# Sht3-V12P0_reg.net
KiCad netlist of a schematic drawn in Altium Designer
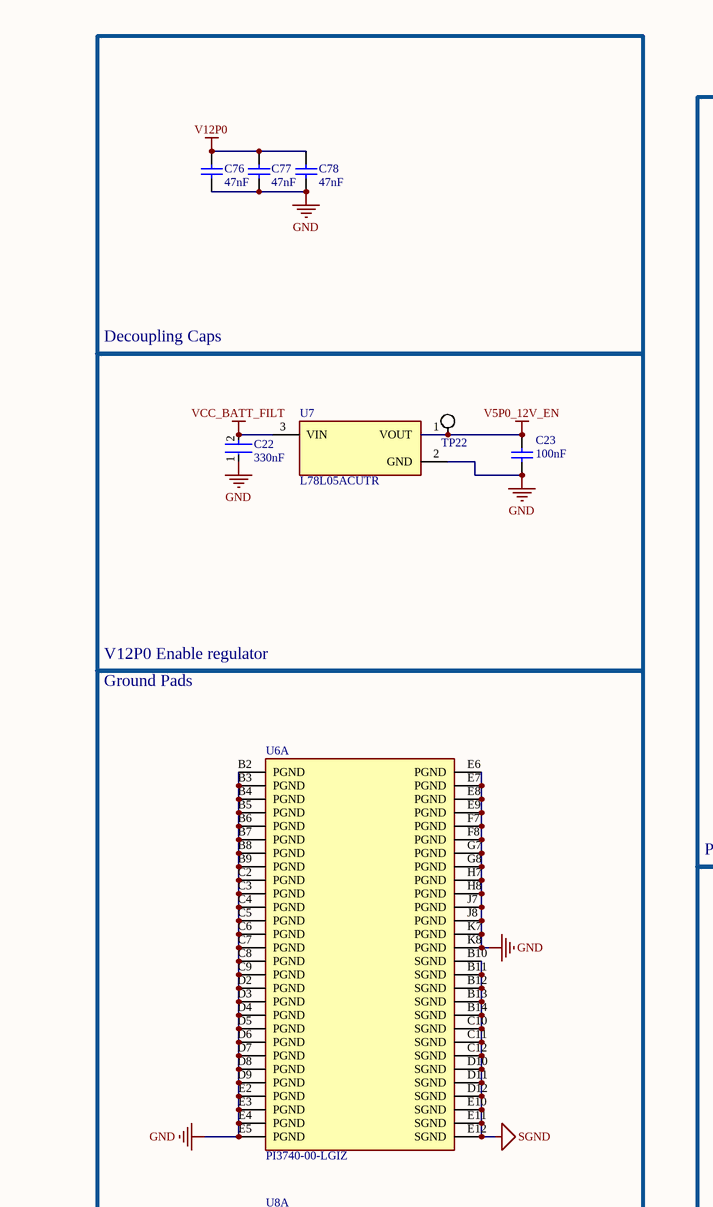
[diagram p0: Sht3-V12P0_reg.SchDoc, top left]
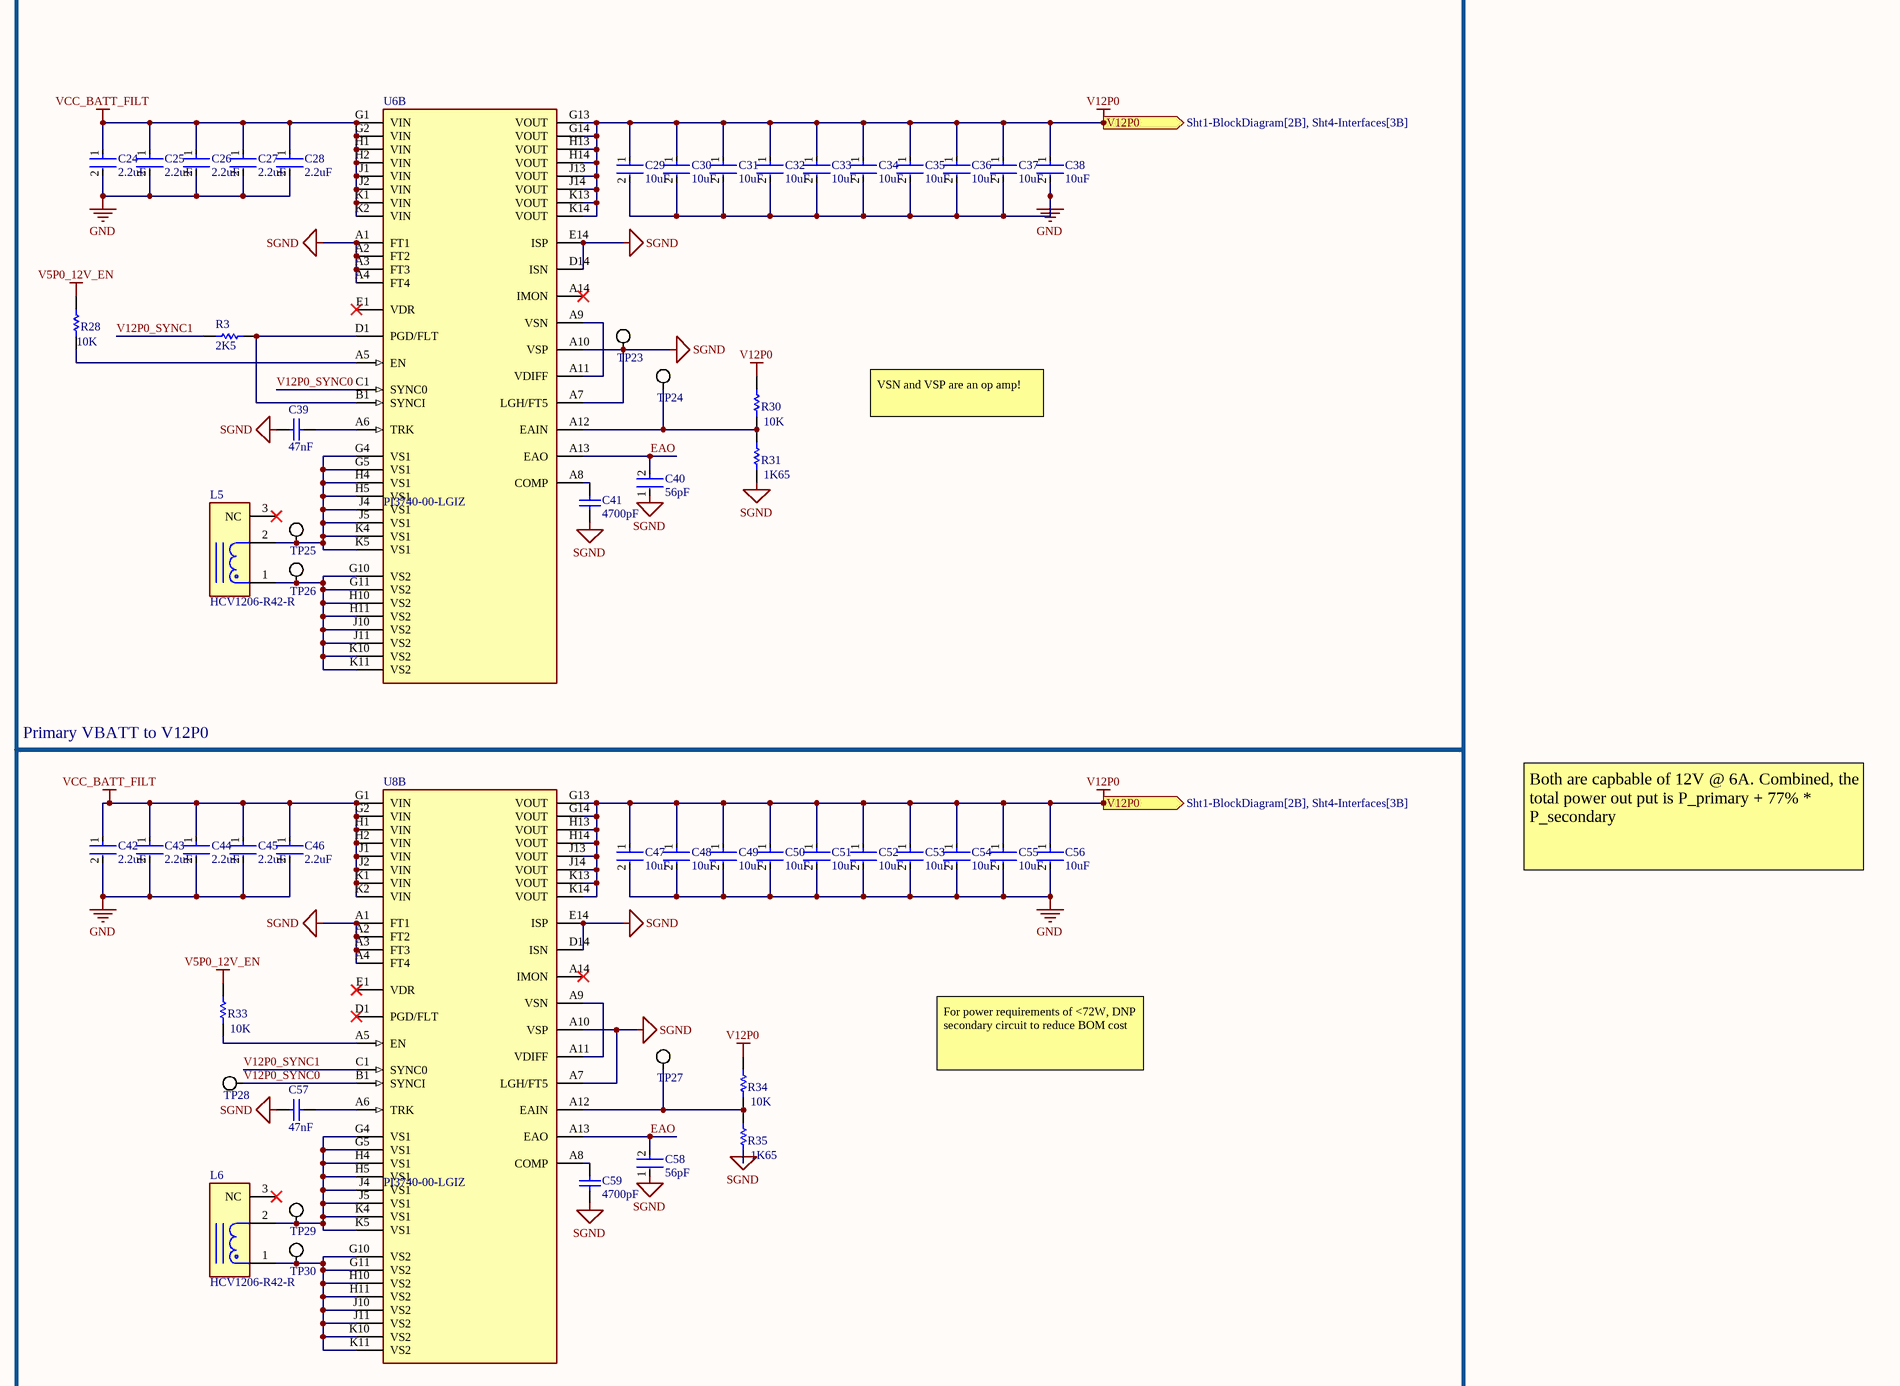
[diagram p1: Sht3-V12P0_reg.SchDoc, top right]
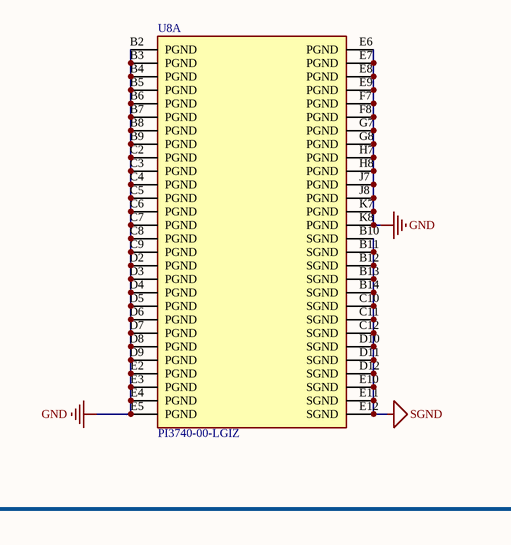
[diagram p2: Sht3-V12P0_reg.SchDoc, bottom left]
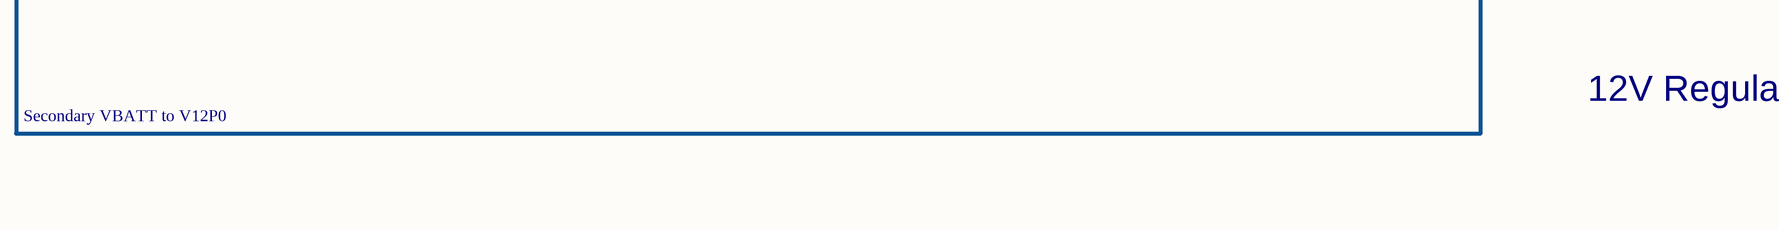
[diagram p3: Sht3-V12P0_reg.SchDoc, bottom right]

(export (version "E")
  (design (tool "Eeschema 10.0.6"))
  (components
    (comp (ref "C22")
      (value "330nF")
      (footprint "FP-C1608-080-0_1-IPC_A")
      (description "Multilayer Ceramic Capacitors 330nF ±10% 50V X7R SMD 0603")
      (fields (field (name "TOLERANCE") "10%") (field (name "VOLTAGE") "50V"))
      (libsource (lib "Altium Content Vault") (part "236180d848d6139a670b325ea6854c9"))
    )
    (comp (ref "C23")
      (value "100nF")
      (footprint "CAPC0603(1608)100_L")
      (description "CAP 100nF 100V ±10% 0603 (1608 Metric) Thickness 1mm SMD")
      (fields (field (name "TOLERANCE") "Â±10%"))
      (libsource (lib "Altium Content Vault") (part "CAP"))
    )
    (comp (ref "C24")
      (value "2.2uF")
      (footprint "FP-1210-L_3_3_0_4-W_2_5_0-IPC_B")
      (description "General Purpose Ceramic Capacitor, 1210, 2.2uF, 10%, X7R, 15%, 100V")
      (fields (field (name "TOLERANCE") "10%") (field (name "VOLTAGE") "100V"))
      (libsource (lib "Altium Content Vault") (part "b4654b650e69147ec39a6b967a45e02"))
    )
    (comp (ref "C25")
      (value "2.2uF")
      (footprint "FP-1210-L_3_3_0_4-W_2_5_0-IPC_B")
      (description "General Purpose Ceramic Capacitor, 1210, 2.2uF, 10%, X7R, 15%, 100V")
      (fields (field (name "TOLERANCE") "10%") (field (name "VOLTAGE") "100V"))
      (libsource (lib "Altium Content Vault") (part "b4654b650e69147ec39a6b967a45e02"))
    )
    (comp (ref "C26")
      (value "2.2uF")
      (footprint "FP-1210-L_3_3_0_4-W_2_5_0-IPC_B")
      (description "General Purpose Ceramic Capacitor, 1210, 2.2uF, 10%, X7R, 15%, 100V")
      (fields (field (name "TOLERANCE") "10%") (field (name "VOLTAGE") "100V"))
      (libsource (lib "Altium Content Vault") (part "b4654b650e69147ec39a6b967a45e02"))
    )
    (comp (ref "C27")
      (value "2.2uF")
      (footprint "FP-1210-L_3_3_0_4-W_2_5_0-IPC_B")
      (description "General Purpose Ceramic Capacitor, 1210, 2.2uF, 10%, X7R, 15%, 100V")
      (fields (field (name "TOLERANCE") "10%") (field (name "VOLTAGE") "100V"))
      (libsource (lib "Altium Content Vault") (part "b4654b650e69147ec39a6b967a45e02"))
    )
    (comp (ref "C28")
      (value "2.2uF")
      (footprint "FP-1210-L_3_3_0_4-W_2_5_0-IPC_B")
      (description "General Purpose Ceramic Capacitor, 1210, 2.2uF, 10%, X7R, 15%, 100V")
      (fields (field (name "TOLERANCE") "10%") (field (name "VOLTAGE") "100V"))
      (libsource (lib "Altium Content Vault") (part "b4654b650e69147ec39a6b967a45e02"))
    )
    (comp (ref "C29")
      (value "10uF")
      (footprint "FP-GRM32-MFG")
      (description "CAP CER 10UF 50V X7R 1210")
      (fields (field (name "TOLERANCE") "10%") (field (name "MANUFACTURER PART NUMBER") "GRM32ER71H106KA12L"))
      (libsource (lib "Altium Content Vault") (part "11868f565c42a9108669ba33697ecf6"))
    )
    (comp (ref "C30")
      (value "10uF")
      (footprint "FP-GRM32-MFG")
      (description "CAP CER 10UF 50V X7R 1210")
      (fields (field (name "TOLERANCE") "10%") (field (name "MANUFACTURER PART NUMBER") "GRM32ER71H106KA12L"))
      (libsource (lib "Altium Content Vault") (part "11868f565c42a9108669ba33697ecf6"))
    )
    (comp (ref "C31")
      (value "10uF")
      (footprint "FP-GRM32-MFG")
      (description "CAP CER 10UF 50V X7R 1210")
      (fields (field (name "TOLERANCE") "10%") (field (name "MANUFACTURER PART NUMBER") "GRM32ER71H106KA12L"))
      (libsource (lib "Altium Content Vault") (part "11868f565c42a9108669ba33697ecf6"))
    )
    (comp (ref "C32")
      (value "10uF")
      (footprint "FP-GRM32-MFG")
      (description "CAP CER 10UF 50V X7R 1210")
      (fields (field (name "TOLERANCE") "10%") (field (name "MANUFACTURER PART NUMBER") "GRM32ER71H106KA12L"))
      (libsource (lib "Altium Content Vault") (part "11868f565c42a9108669ba33697ecf6"))
    )
    (comp (ref "C33")
      (value "10uF")
      (footprint "FP-GRM32-MFG")
      (description "CAP CER 10UF 50V X7R 1210")
      (fields (field (name "TOLERANCE") "10%") (field (name "MANUFACTURER PART NUMBER") "GRM32ER71H106KA12L"))
      (libsource (lib "Altium Content Vault") (part "11868f565c42a9108669ba33697ecf6"))
    )
    (comp (ref "C34")
      (value "10uF")
      (footprint "FP-GRM32-MFG")
      (description "CAP CER 10UF 50V X7R 1210")
      (fields (field (name "TOLERANCE") "10%") (field (name "MANUFACTURER PART NUMBER") "GRM32ER71H106KA12L"))
      (libsource (lib "Altium Content Vault") (part "11868f565c42a9108669ba33697ecf6"))
    )
    (comp (ref "C35")
      (value "10uF")
      (footprint "FP-GRM32-MFG")
      (description "CAP CER 10UF 50V X7R 1210")
      (fields (field (name "TOLERANCE") "10%") (field (name "MANUFACTURER PART NUMBER") "GRM32ER71H106KA12L"))
      (libsource (lib "Altium Content Vault") (part "11868f565c42a9108669ba33697ecf6"))
    )
    (comp (ref "C36")
      (value "10uF")
      (footprint "FP-GRM32-MFG")
      (description "CAP CER 10UF 50V X7R 1210")
      (fields (field (name "TOLERANCE") "10%") (field (name "MANUFACTURER PART NUMBER") "GRM32ER71H106KA12L"))
      (libsource (lib "Altium Content Vault") (part "11868f565c42a9108669ba33697ecf6"))
    )
    (comp (ref "C37")
      (value "10uF")
      (footprint "FP-GRM32-MFG")
      (description "CAP CER 10UF 50V X7R 1210")
      (fields (field (name "TOLERANCE") "10%") (field (name "MANUFACTURER PART NUMBER") "GRM32ER71H106KA12L"))
      (libsource (lib "Altium Content Vault") (part "11868f565c42a9108669ba33697ecf6"))
    )
    (comp (ref "C38")
      (value "10uF")
      (footprint "FP-GRM32-MFG")
      (description "CAP CER 10UF 50V X7R 1210")
      (fields (field (name "TOLERANCE") "10%") (field (name "MANUFACTURER PART NUMBER") "GRM32ER71H106KA12L"))
      (libsource (lib "Altium Content Vault") (part "11868f565c42a9108669ba33697ecf6"))
    )
    (comp (ref "C39")
      (value "47nF")
      (footprint "CAPC1608X90X35LL10T15")
      (description "47nF 0603")
      (fields (field (name "MANUFACTURER") "Murata") (field (name "PART NUMBER") "GRM188R71E473KA01D"))
      (libsource (lib "Altium Content Vault") (part "CAP"))
    )
    (comp (ref "C40")
      (value "56pF")
      (footprint "FP-C1608-080-0_1-IPC_C")
      (description "Multilayer Ceramic Capacitors 56pF ±5% 50V C0G SMD 0603")
      (fields (field (name "TOLERANCE") "5%"))
      (libsource (lib "Altium Content Vault") (part "236180d848d6139a670b325ea6854c9"))
    )
    (comp (ref "C41")
      (value "4700pF")
      (footprint "CAPC1608X90X35ML10T15")
      (description "4700pF 0603")
      (fields (field (name "PART NUMBER") "GRM188R72A472KA01D") (field (name "MANUFACTURER") "Murata"))
      (libsource (lib "Altium Content Vault") (part "CAP"))
    )
    (comp (ref "C42")
      (value "2.2uF")
      (footprint "FP-1210-L_3_3_0_4-W_2_5_0-IPC_B")
      (description "General Purpose Ceramic Capacitor, 1210, 2.2uF, 10%, X7R, 15%, 100V")
      (fields (field (name "TOLERANCE") "10%") (field (name "VOLTAGE") "100V"))
      (libsource (lib "Altium Content Vault") (part "b4654b650e69147ec39a6b967a45e02"))
    )
    (comp (ref "C43")
      (value "2.2uF")
      (footprint "FP-1210-L_3_3_0_4-W_2_5_0-IPC_B")
      (description "General Purpose Ceramic Capacitor, 1210, 2.2uF, 10%, X7R, 15%, 100V")
      (fields (field (name "TOLERANCE") "10%") (field (name "VOLTAGE") "100V"))
      (libsource (lib "Altium Content Vault") (part "b4654b650e69147ec39a6b967a45e02"))
    )
    (comp (ref "C44")
      (value "2.2uF")
      (footprint "FP-1210-L_3_3_0_4-W_2_5_0-IPC_B")
      (description "General Purpose Ceramic Capacitor, 1210, 2.2uF, 10%, X7R, 15%, 100V")
      (fields (field (name "TOLERANCE") "10%") (field (name "VOLTAGE") "100V"))
      (libsource (lib "Altium Content Vault") (part "b4654b650e69147ec39a6b967a45e02"))
    )
    (comp (ref "C45")
      (value "2.2uF")
      (footprint "FP-1210-L_3_3_0_4-W_2_5_0-IPC_B")
      (description "General Purpose Ceramic Capacitor, 1210, 2.2uF, 10%, X7R, 15%, 100V")
      (fields (field (name "TOLERANCE") "10%") (field (name "VOLTAGE") "100V"))
      (libsource (lib "Altium Content Vault") (part "b4654b650e69147ec39a6b967a45e02"))
    )
    (comp (ref "C46")
      (value "2.2uF")
      (footprint "FP-1210-L_3_3_0_4-W_2_5_0-IPC_B")
      (description "General Purpose Ceramic Capacitor, 1210, 2.2uF, 10%, X7R, 15%, 100V")
      (fields (field (name "TOLERANCE") "10%") (field (name "VOLTAGE") "100V"))
      (libsource (lib "Altium Content Vault") (part "b4654b650e69147ec39a6b967a45e02"))
    )
    (comp (ref "C47")
      (value "10uF")
      (footprint "FP-GRM32-MFG")
      (description "CAP CER 10UF 50V X7R 1210")
      (fields (field (name "TOLERANCE") "10%") (field (name "MANUFACTURER PART NUMBER") "GRM32ER71H106KA12L"))
      (libsource (lib "Altium Content Vault") (part "11868f565c42a9108669ba33697ecf6"))
    )
    (comp (ref "C48")
      (value "10uF")
      (footprint "FP-GRM32-MFG")
      (description "CAP CER 10UF 50V X7R 1210")
      (fields (field (name "TOLERANCE") "10%") (field (name "MANUFACTURER PART NUMBER") "GRM32ER71H106KA12L"))
      (libsource (lib "Altium Content Vault") (part "11868f565c42a9108669ba33697ecf6"))
    )
    (comp (ref "C49")
      (value "10uF")
      (footprint "FP-GRM32-MFG")
      (description "CAP CER 10UF 50V X7R 1210")
      (fields (field (name "TOLERANCE") "10%") (field (name "MANUFACTURER PART NUMBER") "GRM32ER71H106KA12L"))
      (libsource (lib "Altium Content Vault") (part "11868f565c42a9108669ba33697ecf6"))
    )
    (comp (ref "C50")
      (value "10uF")
      (footprint "FP-GRM32-MFG")
      (description "CAP CER 10UF 50V X7R 1210")
      (fields (field (name "TOLERANCE") "10%") (field (name "MANUFACTURER PART NUMBER") "GRM32ER71H106KA12L"))
      (libsource (lib "Altium Content Vault") (part "11868f565c42a9108669ba33697ecf6"))
    )
    (comp (ref "C51")
      (value "10uF")
      (footprint "FP-GRM32-MFG")
      (description "CAP CER 10UF 50V X7R 1210")
      (fields (field (name "TOLERANCE") "10%") (field (name "MANUFACTURER PART NUMBER") "GRM32ER71H106KA12L"))
      (libsource (lib "Altium Content Vault") (part "11868f565c42a9108669ba33697ecf6"))
    )
    (comp (ref "C52")
      (value "10uF")
      (footprint "FP-GRM32-MFG")
      (description "CAP CER 10UF 50V X7R 1210")
      (fields (field (name "TOLERANCE") "10%") (field (name "MANUFACTURER PART NUMBER") "GRM32ER71H106KA12L"))
      (libsource (lib "Altium Content Vault") (part "11868f565c42a9108669ba33697ecf6"))
    )
    (comp (ref "C53")
      (value "10uF")
      (footprint "FP-GRM32-MFG")
      (description "CAP CER 10UF 50V X7R 1210")
      (fields (field (name "TOLERANCE") "10%") (field (name "MANUFACTURER PART NUMBER") "GRM32ER71H106KA12L"))
      (libsource (lib "Altium Content Vault") (part "11868f565c42a9108669ba33697ecf6"))
    )
    (comp (ref "C54")
      (value "10uF")
      (footprint "FP-GRM32-MFG")
      (description "CAP CER 10UF 50V X7R 1210")
      (fields (field (name "TOLERANCE") "10%") (field (name "MANUFACTURER PART NUMBER") "GRM32ER71H106KA12L"))
      (libsource (lib "Altium Content Vault") (part "11868f565c42a9108669ba33697ecf6"))
    )
    (comp (ref "C55")
      (value "10uF")
      (footprint "FP-GRM32-MFG")
      (description "CAP CER 10UF 50V X7R 1210")
      (fields (field (name "TOLERANCE") "10%") (field (name "MANUFACTURER PART NUMBER") "GRM32ER71H106KA12L"))
      (libsource (lib "Altium Content Vault") (part "11868f565c42a9108669ba33697ecf6"))
    )
    (comp (ref "C56")
      (value "10uF")
      (footprint "FP-GRM32-MFG")
      (description "CAP CER 10UF 50V X7R 1210")
      (fields (field (name "TOLERANCE") "10%") (field (name "MANUFACTURER PART NUMBER") "GRM32ER71H106KA12L"))
      (libsource (lib "Altium Content Vault") (part "11868f565c42a9108669ba33697ecf6"))
    )
    (comp (ref "C57")
      (value "47nF")
      (footprint "CAPC1608X90X35LL10T15")
      (description "47nF 0603")
      (fields (field (name "MANUFACTURER") "Murata") (field (name "PART NUMBER") "GRM188R71E473KA01D"))
      (libsource (lib "Altium Content Vault") (part "CAP"))
    )
    (comp (ref "C58")
      (value "56pF")
      (footprint "FP-C1608-080-0_1-IPC_C")
      (description "Multilayer Ceramic Capacitors 56pF ±5% 50V C0G SMD 0603")
      (fields (field (name "TOLERANCE") "5%"))
      (libsource (lib "Altium Content Vault") (part "236180d848d6139a670b325ea6854c9"))
    )
    (comp (ref "C59")
      (value "4700pF")
      (footprint "CAPC1608X90X35ML10T15")
      (description "4700pF 0603")
      (fields (field (name "PART NUMBER") "GRM188R72A472KA01D") (field (name "MANUFACTURER") "Murata"))
      (libsource (lib "Altium Content Vault") (part "CAP"))
    )
    (comp (ref "C76")
      (value "47nF")
      (footprint "CAPC1608X90X35LL10T15")
      (description "47nF 0603")
      (fields (field (name "MANUFACTURER") "Murata") (field (name "PART NUMBER") "GRM188R71E473KA01D"))
      (libsource (lib "Altium Content Vault") (part "CAP"))
    )
    (comp (ref "C77")
      (value "47nF")
      (footprint "CAPC1608X90X35LL10T15")
      (description "47nF 0603")
      (fields (field (name "MANUFACTURER") "Murata") (field (name "PART NUMBER") "GRM188R71E473KA01D"))
      (libsource (lib "Altium Content Vault") (part "CAP"))
    )
    (comp (ref "C78")
      (value "47nF")
      (footprint "CAPC1608X90X35LL10T15")
      (description "47nF 0603")
      (fields (field (name "MANUFACTURER") "Murata") (field (name "PART NUMBER") "GRM188R71E473KA01D"))
      (libsource (lib "Altium Content Vault") (part "CAP"))
    )
    (comp (ref "L5")
      (value "HCV1206-R42-R")
      (footprint "FP-HCV1206-R42-R-MFG")
      (description "HCV1206-R42-R -FIXED IND 420NH 16A 3.15 MOHM")
      (fields (field (name "TOLERANCE") "10%"))
      (libsource (lib "Altium Content Vault") (part "37f71924ba6560a669f32c2ee7c419d"))
    )
    (comp (ref "L6")
      (value "HCV1206-R42-R")
      (footprint "FP-HCV1206-R42-R-MFG")
      (description "FIXED IND 420NH 16A 3.15 MOHM")
      (fields (field (name "TOLERANCE") "10%"))
      (libsource (lib "Altium Content Vault") (part "37f71924ba6560a669f32c2ee7c419d"))
    )
    (comp (ref "R3")
      (value "2K5")
      (footprint "RESC1608X55X25NL10T15")
      (description "2.5K 0603")
      (fields (field (name "MANUFACTURER") "Yageo") (field (name "PART NUMBER") "RC0603FR-072K55L"))
      (libsource (lib "Altium Content Vault") (part "RES"))
    )
    (comp (ref "R28")
      (value "10K")
      (footprint "RESC1609X50X30NL8T20")
      (description "Chip Resistor, 10 KOhm, +/- 1%, 100 mW, -55 to 155 degC, 0603 (1608 Metric), RoHS, Tape and Reel")
      (fields (field (name "MANUFACTURER") "Vishay Semiconductor"))
      (libsource (lib "Altium Content Vault") (part "RES-2"))
    )
    (comp (ref "R30")
      (value "10K")
      (footprint "RESC1609X50X30NL8T20")
      (description "Chip Resistor, 10 KOhm, +/- 1%, 100 mW, -55 to 155 degC, 0603 (1608 Metric), RoHS, Tape and Reel")
      (fields (field (name "MANUFACTURER") "Vishay Semiconductor"))
      (libsource (lib "Altium Content Vault") (part "RES-2"))
    )
    (comp (ref "R31")
      (value "1K65")
      (footprint "RESC1608X55X25ML10T15")
      (description "1.65k 0603")
      (fields (field (name "PART NUMBER") "RC0603FR-071K65L") (field (name "MANUFACTURER") "Yageo"))
      (libsource (lib "Altium Content Vault") (part "RES"))
    )
    (comp (ref "R33")
      (value "10K")
      (footprint "RESC1609X50X30NL8T20")
      (description "Chip Resistor, 10 KOhm, +/- 1%, 100 mW, -55 to 155 degC, 0603 (1608 Metric), RoHS, Tape and Reel")
      (fields (field (name "MANUFACTURER") "Vishay Semiconductor"))
      (libsource (lib "Altium Content Vault") (part "RES-2"))
    )
    (comp (ref "R34")
      (value "10K")
      (footprint "RESC1609X50X30NL8T20")
      (description "Chip Resistor, 10 KOhm, +/- 1%, 100 mW, -55 to 155 degC, 0603 (1608 Metric), RoHS, Tape and Reel")
      (fields (field (name "MANUFACTURER") "Vishay Semiconductor"))
      (libsource (lib "Altium Content Vault") (part "RES-2"))
    )
    (comp (ref "R35")
      (value "1K65")
      (footprint "RESC1608X55X25ML10T15")
      (description "1.65k 0603")
      (fields (field (name "PART NUMBER") "RC0603FR-071K65L") (field (name "MANUFACTURER") "Yageo"))
      (libsource (lib "Altium Content Vault") (part "RES"))
    )
    (comp (ref "TP22")
      (value "Test Point Pad")
      (footprint "Test Point Pad")
      (description "Test point, Pad, 28 mil")
      (libsource (lib "CMR_PCB_Components") (part "Test Point Pad"))
    )
    (comp (ref "TP23")
      (value "Test Point Pad")
      (footprint "Test Point Pad")
      (description "Test point, Pad, 28 mil")
      (libsource (lib "CMR_PCB_Components") (part "Test Point Pad"))
    )
    (comp (ref "TP24")
      (value "Test Point Pad")
      (footprint "Test Point Pad")
      (description "Test point, Pad, 28 mil")
      (libsource (lib "CMR_PCB_Components") (part "Test Point Pad"))
    )
    (comp (ref "TP25")
      (value "Test Point Pad")
      (footprint "Test Point Pad")
      (description "Test point, Pad, 28 mil")
      (libsource (lib "CMR_PCB_Components") (part "Test Point Pad"))
    )
    (comp (ref "TP26")
      (value "Test Point Pad")
      (footprint "Test Point Pad")
      (description "Test point, Pad, 28 mil")
      (libsource (lib "CMR_PCB_Components") (part "Test Point Pad"))
    )
    (comp (ref "TP27")
      (value "Test Point Pad")
      (footprint "Test Point Pad")
      (description "Test point, Pad, 28 mil")
      (libsource (lib "CMR_PCB_Components") (part "Test Point Pad"))
    )
    (comp (ref "TP28")
      (value "Test Point Pad")
      (footprint "Test Point Pad")
      (description "Test point, Pad, 28 mil")
      (libsource (lib "CMR_PCB_Components") (part "Test Point Pad"))
    )
    (comp (ref "TP29")
      (value "Test Point Pad")
      (footprint "Test Point Pad")
      (description "Test point, Pad, 28 mil")
      (libsource (lib "CMR_PCB_Components") (part "Test Point Pad"))
    )
    (comp (ref "TP30")
      (value "Test Point Pad")
      (footprint "Test Point Pad")
      (description "Test point, Pad, 28 mil")
      (libsource (lib "CMR_PCB_Components") (part "Test Point Pad"))
    )
    (comp (ref "U6")
      (value "PI3740-00-LGIZ")
      (footprint "FP-PI3740-00-LGIZ-MFG")
      (description "DC DC CONVERTER 10-50V")
      (libsource (lib "Altium Content Vault") (part "1066ae71189b305fd66a514a457717d"))
    )
    (comp (ref "U7")
      (value "L78L05ACUTR")
      (footprint "FP-SOT-89-7098166-MFG")
      (description "IC REG LINEAR 5V 100MA SOT89-3")
      (libsource (lib "Altium Content Vault") (part "ae6bee9076d4e2dbe8e374331bf90c1"))
    )
    (comp (ref "U8")
      (value "PI3740-00-LGIZ")
      (footprint "FP-PI3740-00-LGIZ-MFG")
      (description "DC DC CONVERTER 10-50V")
      (libsource (lib "Altium Content Vault") (part "1066ae71189b305fd66a514a457717d"))
    )
  )
  (nets
    (net (code "1") (name "/EAO") (class "Default")
      (node (ref "C40") (pin "2") (pinfunction "2_2") (pintype "passive"))
      (node (ref "C58") (pin "2") (pinfunction "2_2") (pintype "passive"))
      (node (ref "U6") (pin "A13") (pinfunction "EAO_A13") (pintype "passive"))
      (node (ref "U8") (pin "A13") (pinfunction "EAO_A13") (pintype "passive"))
    )
    (net (code "2") (name "/V12P0_SYNC0") (class "Default")
      (node (ref "TP28") (pin "1") (pinfunction "1_1") (pintype "passive"))
      (node (ref "U6") (pin "C1") (pinfunction "SYNC0_C1") (pintype "input"))
      (node (ref "U8") (pin "B1") (pinfunction "SYNCI_B1") (pintype "input"))
    )
    (net (code "3") (name "/V12P0_SYNC1") (class "Default")
      (node (ref "R3") (pin "1") (pinfunction "1_1") (pintype "passive"))
      (node (ref "U8") (pin "C1") (pinfunction "SYNC0_C1") (pintype "input"))
    )
    (net (code "4") (name "GND") (class "Default")
      (node (ref "C22") (pin "1") (pinfunction "1_1") (pintype "passive"))
      (node (ref "C23") (pin "1") (pinfunction "1_1") (pintype "passive"))
      (node (ref "C24") (pin "2") (pinfunction "2_2") (pintype "passive"))
      (node (ref "C25") (pin "2") (pinfunction "2_2") (pintype "passive"))
      (node (ref "C26") (pin "2") (pinfunction "2_2") (pintype "passive"))
      (node (ref "C27") (pin "2") (pinfunction "2_2") (pintype "passive"))
      (node (ref "C28") (pin "2") (pinfunction "2_2") (pintype "passive"))
      (node (ref "C29") (pin "2") (pinfunction "2_2") (pintype "passive"))
      (node (ref "C30") (pin "2") (pinfunction "2_2") (pintype "passive"))
      (node (ref "C31") (pin "2") (pinfunction "2_2") (pintype "passive"))
      (node (ref "C32") (pin "2") (pinfunction "2_2") (pintype "passive"))
      (node (ref "C33") (pin "2") (pinfunction "2_2") (pintype "passive"))
      (node (ref "C34") (pin "2") (pinfunction "2_2") (pintype "passive"))
      (node (ref "C35") (pin "2") (pinfunction "2_2") (pintype "passive"))
      (node (ref "C36") (pin "2") (pinfunction "2_2") (pintype "passive"))
      (node (ref "C37") (pin "2") (pinfunction "2_2") (pintype "passive"))
      (node (ref "C38") (pin "2") (pinfunction "2_2") (pintype "passive"))
      (node (ref "C42") (pin "2") (pinfunction "2_2") (pintype "passive"))
      (node (ref "C43") (pin "2") (pinfunction "2_2") (pintype "passive"))
      (node (ref "C44") (pin "2") (pinfunction "2_2") (pintype "passive"))
      (node (ref "C45") (pin "2") (pinfunction "2_2") (pintype "passive"))
      (node (ref "C46") (pin "2") (pinfunction "2_2") (pintype "passive"))
      (node (ref "C47") (pin "2") (pinfunction "2_2") (pintype "passive"))
      (node (ref "C48") (pin "2") (pinfunction "2_2") (pintype "passive"))
      (node (ref "C49") (pin "2") (pinfunction "2_2") (pintype "passive"))
      (node (ref "C50") (pin "2") (pinfunction "2_2") (pintype "passive"))
      (node (ref "C51") (pin "2") (pinfunction "2_2") (pintype "passive"))
      (node (ref "C52") (pin "2") (pinfunction "2_2") (pintype "passive"))
      (node (ref "C53") (pin "2") (pinfunction "2_2") (pintype "passive"))
      (node (ref "C54") (pin "2") (pinfunction "2_2") (pintype "passive"))
      (node (ref "C55") (pin "2") (pinfunction "2_2") (pintype "passive"))
      (node (ref "C56") (pin "2") (pinfunction "2_2") (pintype "passive"))
      (node (ref "C76") (pin "1") (pinfunction "1_1") (pintype "passive"))
      (node (ref "C77") (pin "1") (pinfunction "1_1") (pintype "passive"))
      (node (ref "C78") (pin "1") (pinfunction "1_1") (pintype "passive"))
      (node (ref "U6") (pin "B2") (pinfunction "PGND_B2") (pintype "power_in"))
      (node (ref "U6") (pin "B3") (pinfunction "PGND_B3") (pintype "power_in"))
      (node (ref "U6") (pin "B4") (pinfunction "PGND_B4") (pintype "power_in"))
      (node (ref "U6") (pin "B5") (pinfunction "PGND_B5") (pintype "power_in"))
      (node (ref "U6") (pin "B6") (pinfunction "PGND_B6") (pintype "power_in"))
      (node (ref "U6") (pin "B7") (pinfunction "PGND_B7") (pintype "power_in"))
      (node (ref "U6") (pin "B8") (pinfunction "PGND_B8") (pintype "power_in"))
      (node (ref "U6") (pin "B9") (pinfunction "PGND_B9") (pintype "power_in"))
      (node (ref "U6") (pin "C2") (pinfunction "PGND_C2") (pintype "power_in"))
      (node (ref "U6") (pin "C3") (pinfunction "PGND_C3") (pintype "power_in"))
      (node (ref "U6") (pin "C4") (pinfunction "PGND_C4") (pintype "power_in"))
      (node (ref "U6") (pin "C5") (pinfunction "PGND_C5") (pintype "power_in"))
      (node (ref "U6") (pin "C6") (pinfunction "PGND_C6") (pintype "power_in"))
      (node (ref "U6") (pin "C7") (pinfunction "PGND_C7") (pintype "power_in"))
      (node (ref "U6") (pin "C8") (pinfunction "PGND_C8") (pintype "power_in"))
      (node (ref "U6") (pin "C9") (pinfunction "PGND_C9") (pintype "power_in"))
      (node (ref "U6") (pin "D2") (pinfunction "PGND_D2") (pintype "power_in"))
      (node (ref "U6") (pin "D3") (pinfunction "PGND_D3") (pintype "power_in"))
      (node (ref "U6") (pin "D4") (pinfunction "PGND_D4") (pintype "power_in"))
      (node (ref "U6") (pin "D5") (pinfunction "PGND_D5") (pintype "power_in"))
      (node (ref "U6") (pin "D6") (pinfunction "PGND_D6") (pintype "power_in"))
      (node (ref "U6") (pin "D7") (pinfunction "PGND_D7") (pintype "power_in"))
      (node (ref "U6") (pin "D8") (pinfunction "PGND_D8") (pintype "power_in"))
      (node (ref "U6") (pin "D9") (pinfunction "PGND_D9") (pintype "power_in"))
      (node (ref "U6") (pin "E2") (pinfunction "PGND_E2") (pintype "power_in"))
      (node (ref "U6") (pin "E3") (pinfunction "PGND_E3") (pintype "power_in"))
      (node (ref "U6") (pin "E4") (pinfunction "PGND_E4") (pintype "power_in"))
      (node (ref "U6") (pin "E5") (pinfunction "PGND_E5") (pintype "power_in"))
      (node (ref "U6") (pin "E6") (pinfunction "PGND_E6") (pintype "power_in"))
      (node (ref "U6") (pin "E7") (pinfunction "PGND_E7") (pintype "power_in"))
      (node (ref "U6") (pin "E8") (pinfunction "PGND_E8") (pintype "power_in"))
      (node (ref "U6") (pin "E9") (pinfunction "PGND_E9") (pintype "power_in"))
      (node (ref "U6") (pin "F7") (pinfunction "PGND_F7") (pintype "power_in"))
      (node (ref "U6") (pin "F8") (pinfunction "PGND_F8") (pintype "power_in"))
      (node (ref "U6") (pin "G7") (pinfunction "PGND_G7") (pintype "power_in"))
      (node (ref "U6") (pin "G8") (pinfunction "PGND_G8") (pintype "power_in"))
      (node (ref "U6") (pin "H7") (pinfunction "PGND_H7") (pintype "power_in"))
      (node (ref "U6") (pin "H8") (pinfunction "PGND_H8") (pintype "power_in"))
      (node (ref "U6") (pin "J7") (pinfunction "PGND_J7") (pintype "power_in"))
      (node (ref "U6") (pin "J8") (pinfunction "PGND_J8") (pintype "power_in"))
      (node (ref "U6") (pin "K7") (pinfunction "PGND_K7") (pintype "power_in"))
      (node (ref "U6") (pin "K8") (pinfunction "PGND_K8") (pintype "power_in"))
      (node (ref "U7") (pin "2") (pinfunction "GND_2") (pintype "power_in"))
      (node (ref "U8") (pin "B2") (pinfunction "PGND_B2") (pintype "power_in"))
      (node (ref "U8") (pin "B3") (pinfunction "PGND_B3") (pintype "power_in"))
      (node (ref "U8") (pin "B4") (pinfunction "PGND_B4") (pintype "power_in"))
      (node (ref "U8") (pin "B5") (pinfunction "PGND_B5") (pintype "power_in"))
      (node (ref "U8") (pin "B6") (pinfunction "PGND_B6") (pintype "power_in"))
      (node (ref "U8") (pin "B7") (pinfunction "PGND_B7") (pintype "power_in"))
      (node (ref "U8") (pin "B8") (pinfunction "PGND_B8") (pintype "power_in"))
      (node (ref "U8") (pin "B9") (pinfunction "PGND_B9") (pintype "power_in"))
      (node (ref "U8") (pin "C2") (pinfunction "PGND_C2") (pintype "power_in"))
      (node (ref "U8") (pin "C3") (pinfunction "PGND_C3") (pintype "power_in"))
      (node (ref "U8") (pin "C4") (pinfunction "PGND_C4") (pintype "power_in"))
      (node (ref "U8") (pin "C5") (pinfunction "PGND_C5") (pintype "power_in"))
      (node (ref "U8") (pin "C6") (pinfunction "PGND_C6") (pintype "power_in"))
      (node (ref "U8") (pin "C7") (pinfunction "PGND_C7") (pintype "power_in"))
      (node (ref "U8") (pin "C8") (pinfunction "PGND_C8") (pintype "power_in"))
      (node (ref "U8") (pin "C9") (pinfunction "PGND_C9") (pintype "power_in"))
      (node (ref "U8") (pin "D2") (pinfunction "PGND_D2") (pintype "power_in"))
      (node (ref "U8") (pin "D3") (pinfunction "PGND_D3") (pintype "power_in"))
      (node (ref "U8") (pin "D4") (pinfunction "PGND_D4") (pintype "power_in"))
      (node (ref "U8") (pin "D5") (pinfunction "PGND_D5") (pintype "power_in"))
      (node (ref "U8") (pin "D6") (pinfunction "PGND_D6") (pintype "power_in"))
      (node (ref "U8") (pin "D7") (pinfunction "PGND_D7") (pintype "power_in"))
      (node (ref "U8") (pin "D8") (pinfunction "PGND_D8") (pintype "power_in"))
      (node (ref "U8") (pin "D9") (pinfunction "PGND_D9") (pintype "power_in"))
      (node (ref "U8") (pin "E2") (pinfunction "PGND_E2") (pintype "power_in"))
      (node (ref "U8") (pin "E3") (pinfunction "PGND_E3") (pintype "power_in"))
      (node (ref "U8") (pin "E4") (pinfunction "PGND_E4") (pintype "power_in"))
      (node (ref "U8") (pin "E5") (pinfunction "PGND_E5") (pintype "power_in"))
      (node (ref "U8") (pin "E6") (pinfunction "PGND_E6") (pintype "power_in"))
      (node (ref "U8") (pin "E7") (pinfunction "PGND_E7") (pintype "power_in"))
      (node (ref "U8") (pin "E8") (pinfunction "PGND_E8") (pintype "power_in"))
      (node (ref "U8") (pin "E9") (pinfunction "PGND_E9") (pintype "power_in"))
      (node (ref "U8") (pin "F7") (pinfunction "PGND_F7") (pintype "power_in"))
      (node (ref "U8") (pin "F8") (pinfunction "PGND_F8") (pintype "power_in"))
      (node (ref "U8") (pin "G7") (pinfunction "PGND_G7") (pintype "power_in"))
      (node (ref "U8") (pin "G8") (pinfunction "PGND_G8") (pintype "power_in"))
      (node (ref "U8") (pin "H7") (pinfunction "PGND_H7") (pintype "power_in"))
      (node (ref "U8") (pin "H8") (pinfunction "PGND_H8") (pintype "power_in"))
      (node (ref "U8") (pin "J7") (pinfunction "PGND_J7") (pintype "power_in"))
      (node (ref "U8") (pin "J8") (pinfunction "PGND_J8") (pintype "power_in"))
      (node (ref "U8") (pin "K7") (pinfunction "PGND_K7") (pintype "power_in"))
      (node (ref "U8") (pin "K8") (pinfunction "PGND_K8") (pintype "power_in"))
    )
    (net (code "5") (name "Net-(L5-Pad1)") (class "Default")
      (node (ref "L5") (pin "1") (pinfunction "1_1") (pintype "passive"))
      (node (ref "TP26") (pin "1") (pinfunction "1_1") (pintype "passive"))
      (node (ref "U6") (pin "G10") (pinfunction "VS2_G10") (pintype "passive"))
      (node (ref "U6") (pin "G11") (pinfunction "VS2_G11") (pintype "passive"))
      (node (ref "U6") (pin "H10") (pinfunction "VS2_H10") (pintype "passive"))
      (node (ref "U6") (pin "H11") (pinfunction "VS2_H11") (pintype "passive"))
      (node (ref "U6") (pin "J10") (pinfunction "VS2_J10") (pintype "passive"))
      (node (ref "U6") (pin "J11") (pinfunction "VS2_J11") (pintype "passive"))
      (node (ref "U6") (pin "K10") (pinfunction "VS2_K10") (pintype "passive"))
      (node (ref "U6") (pin "K11") (pinfunction "VS2_K11") (pintype "passive"))
    )
    (net (code "6") (name "Net-(L5-Pad2)") (class "Default")
      (node (ref "L5") (pin "2") (pinfunction "2_2") (pintype "passive"))
      (node (ref "TP25") (pin "1") (pinfunction "1_1") (pintype "passive"))
      (node (ref "U6") (pin "G4") (pinfunction "VS1_G4") (pintype "passive"))
      (node (ref "U6") (pin "G5") (pinfunction "VS1_G5") (pintype "passive"))
      (node (ref "U6") (pin "H4") (pinfunction "VS1_H4") (pintype "passive"))
      (node (ref "U6") (pin "H5") (pinfunction "VS1_H5") (pintype "passive"))
      (node (ref "U6") (pin "J4") (pinfunction "VS1_J4") (pintype "passive"))
      (node (ref "U6") (pin "J5") (pinfunction "VS1_J5") (pintype "passive"))
      (node (ref "U6") (pin "K4") (pinfunction "VS1_K4") (pintype "passive"))
      (node (ref "U6") (pin "K5") (pinfunction "VS1_K5") (pintype "passive"))
    )
    (net (code "7") (name "Net-(L6-Pad1)") (class "Default")
      (node (ref "L6") (pin "1") (pinfunction "1_1") (pintype "passive"))
      (node (ref "TP30") (pin "1") (pinfunction "1_1") (pintype "passive"))
      (node (ref "U8") (pin "G10") (pinfunction "VS2_G10") (pintype "passive"))
      (node (ref "U8") (pin "G11") (pinfunction "VS2_G11") (pintype "passive"))
      (node (ref "U8") (pin "H10") (pinfunction "VS2_H10") (pintype "passive"))
      (node (ref "U8") (pin "H11") (pinfunction "VS2_H11") (pintype "passive"))
      (node (ref "U8") (pin "J10") (pinfunction "VS2_J10") (pintype "passive"))
      (node (ref "U8") (pin "J11") (pinfunction "VS2_J11") (pintype "passive"))
      (node (ref "U8") (pin "K10") (pinfunction "VS2_K10") (pintype "passive"))
      (node (ref "U8") (pin "K11") (pinfunction "VS2_K11") (pintype "passive"))
    )
    (net (code "8") (name "Net-(L6-Pad2)") (class "Default")
      (node (ref "L6") (pin "2") (pinfunction "2_2") (pintype "passive"))
      (node (ref "TP29") (pin "1") (pinfunction "1_1") (pintype "passive"))
      (node (ref "U8") (pin "G4") (pinfunction "VS1_G4") (pintype "passive"))
      (node (ref "U8") (pin "G5") (pinfunction "VS1_G5") (pintype "passive"))
      (node (ref "U8") (pin "H4") (pinfunction "VS1_H4") (pintype "passive"))
      (node (ref "U8") (pin "H5") (pinfunction "VS1_H5") (pintype "passive"))
      (node (ref "U8") (pin "J4") (pinfunction "VS1_J4") (pintype "passive"))
      (node (ref "U8") (pin "J5") (pinfunction "VS1_J5") (pintype "passive"))
      (node (ref "U8") (pin "K4") (pinfunction "VS1_K4") (pintype "passive"))
      (node (ref "U8") (pin "K5") (pinfunction "VS1_K5") (pintype "passive"))
    )
    (net (code "9") (name "Net-(U6B-COMP)") (class "Default")
      (node (ref "C41") (pin "2") (pinfunction "2_2") (pintype "passive"))
      (node (ref "U6") (pin "A8") (pinfunction "COMP_A8") (pintype "passive"))
    )
    (net (code "10") (name "Net-(U6B-EAIN)") (class "Default")
      (node (ref "R30") (pin "2") (pinfunction "2_2") (pintype "passive"))
      (node (ref "R31") (pin "1") (pinfunction "1_1") (pintype "passive"))
      (node (ref "TP24") (pin "1") (pinfunction "1_1") (pintype "passive"))
      (node (ref "U6") (pin "A12") (pinfunction "EAIN_A12") (pintype "tri_state"))
    )
    (net (code "11") (name "Net-(U6B-EN)") (class "Default")
      (node (ref "R28") (pin "2") (pinfunction "2_2") (pintype "passive"))
      (node (ref "U6") (pin "A5") (pinfunction "EN_A5") (pintype "input"))
    )
    (net (code "12") (name "Net-(U6B-PGD{slash}FLT)") (class "Default")
      (node (ref "R3") (pin "2") (pinfunction "2_2") (pintype "passive"))
      (node (ref "U6") (pin "B1") (pinfunction "SYNCI_B1") (pintype "input"))
      (node (ref "U6") (pin "D1") (pinfunction "PGD/FLT_D1") (pintype "power_in"))
    )
    (net (code "13") (name "Net-(U6B-TRK)") (class "Default")
      (node (ref "C39") (pin "2") (pinfunction "2_2") (pintype "passive"))
      (node (ref "U6") (pin "A6") (pinfunction "TRK_A6") (pintype "input"))
    )
    (net (code "14") (name "Net-(U6B-VDIFF)") (class "Default")
      (node (ref "U6") (pin "A11") (pinfunction "VDIFF_A11") (pintype "passive"))
      (node (ref "U6") (pin "A9") (pinfunction "VSN_A9") (pintype "tri_state"))
    )
    (net (code "15") (name "Net-(U8B-COMP)") (class "Default")
      (node (ref "C59") (pin "2") (pinfunction "2_2") (pintype "passive"))
      (node (ref "U8") (pin "A8") (pinfunction "COMP_A8") (pintype "passive"))
    )
    (net (code "16") (name "Net-(U8B-EAIN)") (class "Default")
      (node (ref "R34") (pin "2") (pinfunction "2_2") (pintype "passive"))
      (node (ref "R35") (pin "1") (pinfunction "1_1") (pintype "passive"))
      (node (ref "TP27") (pin "1") (pinfunction "1_1") (pintype "passive"))
      (node (ref "U8") (pin "A12") (pinfunction "EAIN_A12") (pintype "tri_state"))
    )
    (net (code "17") (name "Net-(U8B-EN)") (class "Default")
      (node (ref "R33") (pin "2") (pinfunction "2_2") (pintype "passive"))
      (node (ref "U8") (pin "A5") (pinfunction "EN_A5") (pintype "input"))
    )
    (net (code "18") (name "Net-(U8B-TRK)") (class "Default")
      (node (ref "C57") (pin "2") (pinfunction "2_2") (pintype "passive"))
      (node (ref "U8") (pin "A6") (pinfunction "TRK_A6") (pintype "input"))
    )
    (net (code "19") (name "Net-(U8B-VDIFF)") (class "Default")
      (node (ref "U8") (pin "A11") (pinfunction "VDIFF_A11") (pintype "passive"))
      (node (ref "U8") (pin "A9") (pinfunction "VSN_A9") (pintype "tri_state"))
    )
    (net (code "20") (name "SGND") (class "Default")
      (node (ref "C39") (pin "1") (pinfunction "1_1") (pintype "passive"))
      (node (ref "C40") (pin "1") (pinfunction "1_1") (pintype "passive"))
      (node (ref "C41") (pin "1") (pinfunction "1_1") (pintype "passive"))
      (node (ref "C57") (pin "1") (pinfunction "1_1") (pintype "passive"))
      (node (ref "C58") (pin "1") (pinfunction "1_1") (pintype "passive"))
      (node (ref "C59") (pin "1") (pinfunction "1_1") (pintype "passive"))
      (node (ref "R31") (pin "2") (pinfunction "2_2") (pintype "passive"))
      (node (ref "R35") (pin "2") (pinfunction "2_2") (pintype "passive"))
      (node (ref "TP23") (pin "1") (pinfunction "1_1") (pintype "passive"))
      (node (ref "U6") (pin "A1") (pinfunction "FT1_A1") (pintype "passive"))
      (node (ref "U6") (pin "A10") (pinfunction "VSP_A10") (pintype "tri_state"))
      (node (ref "U6") (pin "A2") (pinfunction "FT2_A2") (pintype "passive"))
      (node (ref "U6") (pin "A3") (pinfunction "FT3_A3") (pintype "passive"))
      (node (ref "U6") (pin "A4") (pinfunction "FT4_A4") (pintype "passive"))
      (node (ref "U6") (pin "A7") (pinfunction "LGH/FT5_A7") (pintype "passive"))
      (node (ref "U6") (pin "B10") (pinfunction "SGND_B10") (pintype "power_in"))
      (node (ref "U6") (pin "B11") (pinfunction "SGND_B11") (pintype "power_in"))
      (node (ref "U6") (pin "B12") (pinfunction "SGND_B12") (pintype "power_in"))
      (node (ref "U6") (pin "B13") (pinfunction "SGND_B13") (pintype "power_in"))
      (node (ref "U6") (pin "B14") (pinfunction "SGND_B14") (pintype "power_in"))
      (node (ref "U6") (pin "C10") (pinfunction "SGND_C10") (pintype "power_in"))
      (node (ref "U6") (pin "C11") (pinfunction "SGND_C11") (pintype "power_in"))
      (node (ref "U6") (pin "C12") (pinfunction "SGND_C12") (pintype "power_in"))
      (node (ref "U6") (pin "D10") (pinfunction "SGND_D10") (pintype "power_in"))
      (node (ref "U6") (pin "D11") (pinfunction "SGND_D11") (pintype "power_in"))
      (node (ref "U6") (pin "D12") (pinfunction "SGND_D12") (pintype "power_in"))
      (node (ref "U6") (pin "D14") (pinfunction "ISN_D14") (pintype "tri_state"))
      (node (ref "U6") (pin "E10") (pinfunction "SGND_E10") (pintype "power_in"))
      (node (ref "U6") (pin "E11") (pinfunction "SGND_E11") (pintype "power_in"))
      (node (ref "U6") (pin "E12") (pinfunction "SGND_E12") (pintype "power_in"))
      (node (ref "U6") (pin "E14") (pinfunction "ISP_E14") (pintype "tri_state"))
      (node (ref "U8") (pin "A1") (pinfunction "FT1_A1") (pintype "passive"))
      (node (ref "U8") (pin "A10") (pinfunction "VSP_A10") (pintype "tri_state"))
      (node (ref "U8") (pin "A2") (pinfunction "FT2_A2") (pintype "passive"))
      (node (ref "U8") (pin "A3") (pinfunction "FT3_A3") (pintype "passive"))
      (node (ref "U8") (pin "A4") (pinfunction "FT4_A4") (pintype "passive"))
      (node (ref "U8") (pin "A7") (pinfunction "LGH/FT5_A7") (pintype "passive"))
      (node (ref "U8") (pin "B10") (pinfunction "SGND_B10") (pintype "power_in"))
      (node (ref "U8") (pin "B11") (pinfunction "SGND_B11") (pintype "power_in"))
      (node (ref "U8") (pin "B12") (pinfunction "SGND_B12") (pintype "power_in"))
      (node (ref "U8") (pin "B13") (pinfunction "SGND_B13") (pintype "power_in"))
      (node (ref "U8") (pin "B14") (pinfunction "SGND_B14") (pintype "power_in"))
      (node (ref "U8") (pin "C10") (pinfunction "SGND_C10") (pintype "power_in"))
      (node (ref "U8") (pin "C11") (pinfunction "SGND_C11") (pintype "power_in"))
      (node (ref "U8") (pin "C12") (pinfunction "SGND_C12") (pintype "power_in"))
      (node (ref "U8") (pin "D10") (pinfunction "SGND_D10") (pintype "power_in"))
      (node (ref "U8") (pin "D11") (pinfunction "SGND_D11") (pintype "power_in"))
      (node (ref "U8") (pin "D12") (pinfunction "SGND_D12") (pintype "power_in"))
      (node (ref "U8") (pin "D14") (pinfunction "ISN_D14") (pintype "tri_state"))
      (node (ref "U8") (pin "E10") (pinfunction "SGND_E10") (pintype "power_in"))
      (node (ref "U8") (pin "E11") (pinfunction "SGND_E11") (pintype "power_in"))
      (node (ref "U8") (pin "E12") (pinfunction "SGND_E12") (pintype "power_in"))
      (node (ref "U8") (pin "E14") (pinfunction "ISP_E14") (pintype "tri_state"))
    )
    (net (code "21") (name "V5P0_12V_EN") (class "Default")
      (node (ref "C23") (pin "2") (pinfunction "2_2") (pintype "passive"))
      (node (ref "R28") (pin "1") (pinfunction "1_1") (pintype "passive"))
      (node (ref "R33") (pin "1") (pinfunction "1_1") (pintype "passive"))
      (node (ref "TP22") (pin "1") (pinfunction "1_1") (pintype "passive"))
      (node (ref "U7") (pin "1") (pinfunction "VOUT_1") (pintype "power_in"))
    )
    (net (code "22") (name "V12P0") (class "Default")
      (node (ref "C29") (pin "1") (pinfunction "1_1") (pintype "passive"))
      (node (ref "C30") (pin "1") (pinfunction "1_1") (pintype "passive"))
      (node (ref "C31") (pin "1") (pinfunction "1_1") (pintype "passive"))
      (node (ref "C32") (pin "1") (pinfunction "1_1") (pintype "passive"))
      (node (ref "C33") (pin "1") (pinfunction "1_1") (pintype "passive"))
      (node (ref "C34") (pin "1") (pinfunction "1_1") (pintype "passive"))
      (node (ref "C35") (pin "1") (pinfunction "1_1") (pintype "passive"))
      (node (ref "C36") (pin "1") (pinfunction "1_1") (pintype "passive"))
      (node (ref "C37") (pin "1") (pinfunction "1_1") (pintype "passive"))
      (node (ref "C38") (pin "1") (pinfunction "1_1") (pintype "passive"))
      (node (ref "C47") (pin "1") (pinfunction "1_1") (pintype "passive"))
      (node (ref "C48") (pin "1") (pinfunction "1_1") (pintype "passive"))
      (node (ref "C49") (pin "1") (pinfunction "1_1") (pintype "passive"))
      (node (ref "C50") (pin "1") (pinfunction "1_1") (pintype "passive"))
      (node (ref "C51") (pin "1") (pinfunction "1_1") (pintype "passive"))
      (node (ref "C52") (pin "1") (pinfunction "1_1") (pintype "passive"))
      (node (ref "C53") (pin "1") (pinfunction "1_1") (pintype "passive"))
      (node (ref "C54") (pin "1") (pinfunction "1_1") (pintype "passive"))
      (node (ref "C55") (pin "1") (pinfunction "1_1") (pintype "passive"))
      (node (ref "C56") (pin "1") (pinfunction "1_1") (pintype "passive"))
      (node (ref "C76") (pin "2") (pinfunction "2_2") (pintype "passive"))
      (node (ref "C77") (pin "2") (pinfunction "2_2") (pintype "passive"))
      (node (ref "C78") (pin "2") (pinfunction "2_2") (pintype "passive"))
      (node (ref "R30") (pin "1") (pinfunction "1_1") (pintype "passive"))
      (node (ref "R34") (pin "1") (pinfunction "1_1") (pintype "passive"))
      (node (ref "U6") (pin "G13") (pinfunction "VOUT_G13") (pintype "power_in"))
      (node (ref "U6") (pin "G14") (pinfunction "VOUT_G14") (pintype "power_in"))
      (node (ref "U6") (pin "H13") (pinfunction "VOUT_H13") (pintype "power_in"))
      (node (ref "U6") (pin "H14") (pinfunction "VOUT_H14") (pintype "power_in"))
      (node (ref "U6") (pin "J13") (pinfunction "VOUT_J13") (pintype "power_in"))
      (node (ref "U6") (pin "J14") (pinfunction "VOUT_J14") (pintype "power_in"))
      (node (ref "U6") (pin "K13") (pinfunction "VOUT_K13") (pintype "power_in"))
      (node (ref "U6") (pin "K14") (pinfunction "VOUT_K14") (pintype "power_in"))
      (node (ref "U8") (pin "G13") (pinfunction "VOUT_G13") (pintype "power_in"))
      (node (ref "U8") (pin "G14") (pinfunction "VOUT_G14") (pintype "power_in"))
      (node (ref "U8") (pin "H13") (pinfunction "VOUT_H13") (pintype "power_in"))
      (node (ref "U8") (pin "H14") (pinfunction "VOUT_H14") (pintype "power_in"))
      (node (ref "U8") (pin "J13") (pinfunction "VOUT_J13") (pintype "power_in"))
      (node (ref "U8") (pin "J14") (pinfunction "VOUT_J14") (pintype "power_in"))
      (node (ref "U8") (pin "K13") (pinfunction "VOUT_K13") (pintype "power_in"))
      (node (ref "U8") (pin "K14") (pinfunction "VOUT_K14") (pintype "power_in"))
    )
    (net (code "23") (name "VCC_BATT_FILT") (class "Default")
      (node (ref "C22") (pin "2") (pinfunction "2_2") (pintype "passive"))
      (node (ref "C24") (pin "1") (pinfunction "1_1") (pintype "passive"))
      (node (ref "C25") (pin "1") (pinfunction "1_1") (pintype "passive"))
      (node (ref "C26") (pin "1") (pinfunction "1_1") (pintype "passive"))
      (node (ref "C27") (pin "1") (pinfunction "1_1") (pintype "passive"))
      (node (ref "C28") (pin "1") (pinfunction "1_1") (pintype "passive"))
      (node (ref "C42") (pin "1") (pinfunction "1_1") (pintype "passive"))
      (node (ref "C43") (pin "1") (pinfunction "1_1") (pintype "passive"))
      (node (ref "C44") (pin "1") (pinfunction "1_1") (pintype "passive"))
      (node (ref "C45") (pin "1") (pinfunction "1_1") (pintype "passive"))
      (node (ref "C46") (pin "1") (pinfunction "1_1") (pintype "passive"))
      (node (ref "U6") (pin "G1") (pinfunction "VIN_G1") (pintype "power_in"))
      (node (ref "U6") (pin "G2") (pinfunction "VIN_G2") (pintype "power_in"))
      (node (ref "U6") (pin "H1") (pinfunction "VIN_H1") (pintype "power_in"))
      (node (ref "U6") (pin "H2") (pinfunction "VIN_H2") (pintype "power_in"))
      (node (ref "U6") (pin "J1") (pinfunction "VIN_J1") (pintype "power_in"))
      (node (ref "U6") (pin "J2") (pinfunction "VIN_J2") (pintype "power_in"))
      (node (ref "U6") (pin "K1") (pinfunction "VIN_K1") (pintype "power_in"))
      (node (ref "U6") (pin "K2") (pinfunction "VIN_K2") (pintype "power_in"))
      (node (ref "U7") (pin "3") (pinfunction "VIN_3") (pintype "power_in"))
      (node (ref "U8") (pin "G1") (pinfunction "VIN_G1") (pintype "power_in"))
      (node (ref "U8") (pin "G2") (pinfunction "VIN_G2") (pintype "power_in"))
      (node (ref "U8") (pin "H1") (pinfunction "VIN_H1") (pintype "power_in"))
      (node (ref "U8") (pin "H2") (pinfunction "VIN_H2") (pintype "power_in"))
      (node (ref "U8") (pin "J1") (pinfunction "VIN_J1") (pintype "power_in"))
      (node (ref "U8") (pin "J2") (pinfunction "VIN_J2") (pintype "power_in"))
      (node (ref "U8") (pin "K1") (pinfunction "VIN_K1") (pintype "power_in"))
      (node (ref "U8") (pin "K2") (pinfunction "VIN_K2") (pintype "power_in"))
    )
    (net (code "24") (name "unconnected-(L5-NC-Pad3)") (class "Default")
      (node (ref "L5") (pin "3") (pinfunction "NC_3") (pintype "passive+no_connect"))
    )
    (net (code "25") (name "unconnected-(L6-NC-Pad3)") (class "Default")
      (node (ref "L6") (pin "3") (pinfunction "NC_3") (pintype "passive+no_connect"))
    )
    (net (code "26") (name "unconnected-(U6B-IMON-PadA14)") (class "Default")
      (node (ref "U6") (pin "A14") (pinfunction "IMON_A14") (pintype "passive+no_connect"))
    )
    (net (code "27") (name "unconnected-(U6B-VDR-PadE1)") (class "Default")
      (node (ref "U6") (pin "E1") (pinfunction "VDR_E1") (pintype "power_in+no_connect"))
    )
    (net (code "28") (name "unconnected-(U8B-IMON-PadA14)") (class "Default")
      (node (ref "U8") (pin "A14") (pinfunction "IMON_A14") (pintype "passive+no_connect"))
    )
    (net (code "29") (name "unconnected-(U8B-PGD{slash}FLT-PadD1)") (class "Default")
      (node (ref "U8") (pin "D1") (pinfunction "PGD/FLT_D1") (pintype "power_in+no_connect"))
    )
    (net (code "30") (name "unconnected-(U8B-VDR-PadE1)") (class "Default")
      (node (ref "U8") (pin "E1") (pinfunction "VDR_E1") (pintype "power_in+no_connect"))
    )
  )
)
